# SCH_FIT_MIX_2024-07-01.net
KiCad netlist of a schematic drawn in EasyEDA
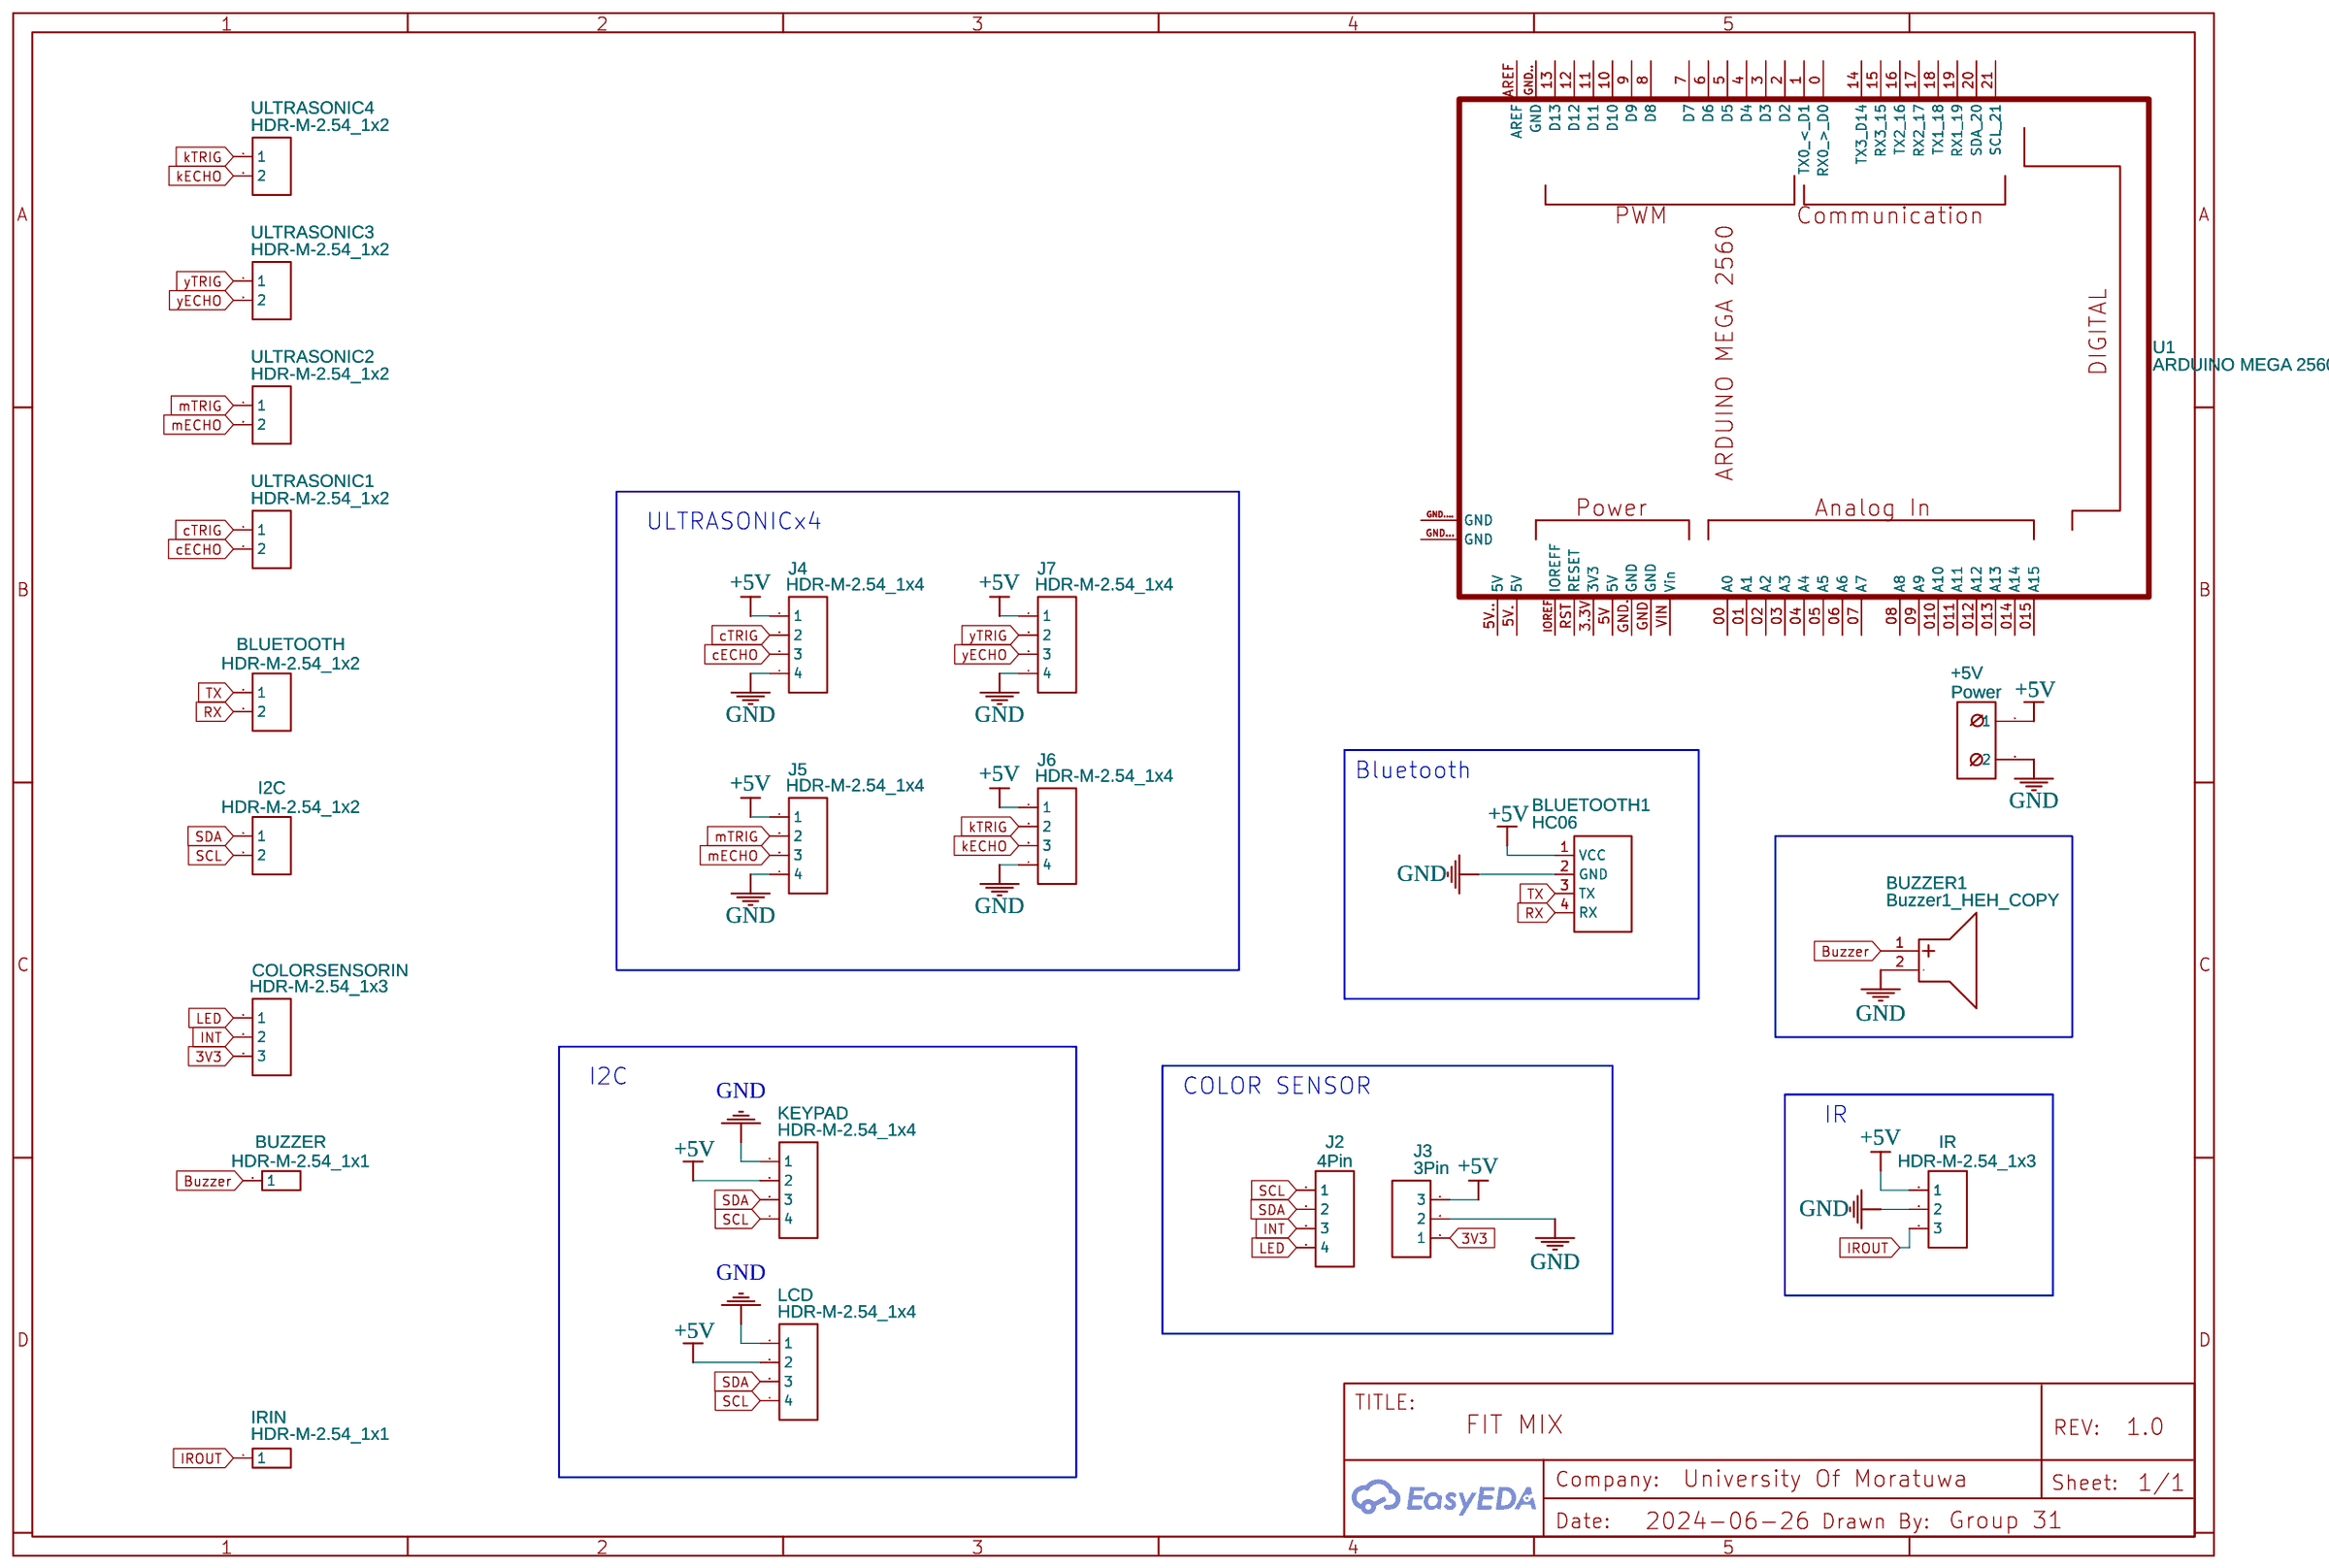
[diagram p0: schematic sheet]

(export (version "E")
  (design (tool "Eeschema 10.0.6"))
  (components
    (comp (ref "+5V") (value "Power") (libsource (lib "") (part "2POSITION_TERMINAL_BLOCK")))
    (comp (ref "BLUETOOTH") (value "HDR-M-2.54_1x2") (libsource (lib "") (part "HDR-M-2.54_1x2_1")))
    (comp (ref "BLUETOOTH1") (value "HC06") (libsource (lib "") (part "HC06")))
    (comp (ref "BUZZER") (value "HDR-M-2.54_1x1") (libsource (lib "") (part "HDR-M-2.54_1x1")))
    (comp (ref "BUZZER1")
      (value "Buzzer1_HEH_COPY")
      (fields (field (name "Manufacturer Part") "-5") (field (name "Manufacturer") "ZLFY"))
      (libsource (lib "") (part "Buzzer1_HEH_COPY"))
    )
    (comp (ref "COLORSENSORIN") (value "HDR-M-2.54_1x3") (libsource (lib "") (part "HDR-M-2.54_1x3")))
    (comp (ref "I2C") (value "HDR-M-2.54_1x2") (libsource (lib "") (part "HDR-M-2.54_1x2_2")))
    (comp (ref "IR") (value "HDR-M-2.54_1x3") (libsource (lib "") (part "HDR-M-2.54_1x3_1")))
    (comp (ref "IRIN") (value "HDR-M-2.54_1x1") (libsource (lib "") (part "HDR-M-2.54_1x1_1")))
    (comp (ref "J2") (value "4Pin") (libsource (lib "") (part "HDR-M-2.54_1x4")))
    (comp (ref "J3") (value "3Pin") (libsource (lib "") (part "HDR-M-2.54_1x3_2")))
    (comp (ref "J4") (value "HDR-M-2.54_1x4") (libsource (lib "") (part "HDR-M-2.54_1x4")))
    (comp (ref "J5") (value "HDR-M-2.54_1x4") (libsource (lib "") (part "HDR-M-2.54_1x4")))
    (comp (ref "J6") (value "HDR-M-2.54_1x4") (libsource (lib "") (part "HDR-M-2.54_1x4")))
    (comp (ref "J7") (value "HDR-M-2.54_1x4") (libsource (lib "") (part "HDR-M-2.54_1x4")))
    (comp (ref "KEYPAD") (value "HDR-M-2.54_1x4") (libsource (lib "") (part "HDR-M-2.54_1x4_2")))
    (comp (ref "LCD") (value "HDR-M-2.54_1x4") (libsource (lib "") (part "HDR-M-2.54_1x4_1")))
    (comp (ref "U1")
      (value "ARDUINO MEGA 2560 R3 V1.0_shella")
      (libsource (lib "") (part "ARDUINO MEGA 2560 R3 V1.0"))
    )
    (comp (ref "ULTRASONIC1") (value "HDR-M-2.54_1x2") (libsource (lib "") (part "HDR-M-2.54_1x2")))
    (comp (ref "ULTRASONIC2") (value "HDR-M-2.54_1x2") (libsource (lib "") (part "HDR-M-2.54_1x2")))
    (comp (ref "ULTRASONIC3") (value "HDR-M-2.54_1x2") (libsource (lib "") (part "HDR-M-2.54_1x2")))
    (comp (ref "ULTRASONIC4") (value "HDR-M-2.54_1x2") (libsource (lib "") (part "HDR-M-2.54_1x2")))
  )
  (nets
    (net (code "1") (name "+5V") (class "Default")
      (node (ref "+5V") (pin "1") (pinfunction "1_1") (pintype "unspecified"))
      (node (ref "BLUETOOTH1") (pin "1") (pinfunction "VCC_1") (pintype "unspecified"))
      (node (ref "IR") (pin "1") (pinfunction "1_1") (pintype "input"))
      (node (ref "J3") (pin "3") (pinfunction "3_3") (pintype "input"))
      (node (ref "J4") (pin "1") (pinfunction "1_1") (pintype "unspecified"))
      (node (ref "J5") (pin "1") (pinfunction "1_1") (pintype "unspecified"))
      (node (ref "J6") (pin "1") (pinfunction "1_1") (pintype "unspecified"))
      (node (ref "J7") (pin "1") (pinfunction "1_1") (pintype "unspecified"))
      (node (ref "KEYPAD") (pin "2") (pinfunction "2_2") (pintype "unspecified"))
      (node (ref "LCD") (pin "2") (pinfunction "2_2") (pintype "unspecified"))
    )
    (net (code "2") (name "3V3") (class "Default")
      (node (ref "COLORSENSORIN") (pin "3") (pinfunction "3_3") (pintype "input"))
      (node (ref "J3") (pin "1") (pinfunction "1_1") (pintype "input"))
    )
    (net (code "3") (name "Buzzer") (class "Default")
      (node (ref "BUZZER") (pin "1") (pinfunction "1_1") (pintype "input"))
      (node (ref "BUZZER1") (pin "1") (pinfunction "+_1") (pintype "unspecified"))
    )
    (net (code "4") (name "GND") (class "Default")
      (node (ref "+5V") (pin "2") (pinfunction "2_2") (pintype "unspecified"))
      (node (ref "BLUETOOTH1") (pin "2") (pinfunction "GND_2") (pintype "unspecified"))
      (node (ref "BUZZER1") (pin "2") (pinfunction "-_2") (pintype "unspecified"))
      (node (ref "IR") (pin "2") (pinfunction "2_2") (pintype "input"))
      (node (ref "J3") (pin "2") (pinfunction "2_2") (pintype "input"))
      (node (ref "J4") (pin "4") (pinfunction "4_4") (pintype "unspecified"))
      (node (ref "J5") (pin "4") (pinfunction "4_4") (pintype "unspecified"))
      (node (ref "J6") (pin "4") (pinfunction "4_4") (pintype "unspecified"))
      (node (ref "J7") (pin "4") (pinfunction "4_4") (pintype "unspecified"))
      (node (ref "KEYPAD") (pin "1") (pinfunction "1_1") (pintype "unspecified"))
      (node (ref "LCD") (pin "1") (pinfunction "1_1") (pintype "unspecified"))
    )
    (net (code "5") (name "INT") (class "Default")
      (node (ref "COLORSENSORIN") (pin "2") (pinfunction "2_2") (pintype "input"))
      (node (ref "J2") (pin "3") (pinfunction "3_3") (pintype "unspecified"))
    )
    (net (code "6") (name "IROUT") (class "Default")
      (node (ref "IR") (pin "3") (pinfunction "3_3") (pintype "input"))
      (node (ref "IRIN") (pin "1") (pinfunction "1_1") (pintype "input"))
    )
    (net (code "7") (name "LED") (class "Default")
      (node (ref "COLORSENSORIN") (pin "1") (pinfunction "1_1") (pintype "input"))
      (node (ref "J2") (pin "4") (pinfunction "4_4") (pintype "unspecified"))
    )
    (net (code "8") (name "RX") (class "Default")
      (node (ref "BLUETOOTH") (pin "2") (pinfunction "2_2") (pintype "unspecified"))
      (node (ref "BLUETOOTH1") (pin "4") (pinfunction "RX_4") (pintype "unspecified"))
    )
    (net (code "9") (name "SCL") (class "Default")
      (node (ref "I2C") (pin "2") (pinfunction "2_2") (pintype "unspecified"))
      (node (ref "J2") (pin "1") (pinfunction "1_1") (pintype "unspecified"))
      (node (ref "KEYPAD") (pin "4") (pinfunction "4_4") (pintype "unspecified"))
      (node (ref "LCD") (pin "4") (pinfunction "4_4") (pintype "unspecified"))
    )
    (net (code "10") (name "SDA") (class "Default")
      (node (ref "I2C") (pin "1") (pinfunction "1_1") (pintype "unspecified"))
      (node (ref "J2") (pin "2") (pinfunction "2_2") (pintype "unspecified"))
      (node (ref "KEYPAD") (pin "3") (pinfunction "3_3") (pintype "unspecified"))
      (node (ref "LCD") (pin "3") (pinfunction "3_3") (pintype "unspecified"))
    )
    (net (code "11") (name "TX") (class "Default")
      (node (ref "BLUETOOTH") (pin "1") (pinfunction "1_1") (pintype "unspecified"))
      (node (ref "BLUETOOTH1") (pin "3") (pinfunction "TX_3") (pintype "unspecified"))
    )
    (net (code "12") (name "cECHO") (class "Default")
      (node (ref "J4") (pin "3") (pinfunction "3_3") (pintype "unspecified"))
      (node (ref "ULTRASONIC1") (pin "2") (pinfunction "2_2") (pintype "unspecified"))
    )
    (net (code "13") (name "cTRIG") (class "Default")
      (node (ref "J4") (pin "2") (pinfunction "2_2") (pintype "unspecified"))
      (node (ref "ULTRASONIC1") (pin "1") (pinfunction "1_1") (pintype "unspecified"))
    )
    (net (code "14") (name "kECHO") (class "Default")
      (node (ref "J6") (pin "3") (pinfunction "3_3") (pintype "unspecified"))
      (node (ref "ULTRASONIC4") (pin "2") (pinfunction "2_2") (pintype "unspecified"))
    )
    (net (code "15") (name "kTRIG") (class "Default")
      (node (ref "J6") (pin "2") (pinfunction "2_2") (pintype "unspecified"))
      (node (ref "ULTRASONIC4") (pin "1") (pinfunction "1_1") (pintype "unspecified"))
    )
    (net (code "16") (name "mECHO") (class "Default")
      (node (ref "J5") (pin "3") (pinfunction "3_3") (pintype "unspecified"))
      (node (ref "ULTRASONIC2") (pin "2") (pinfunction "2_2") (pintype "unspecified"))
    )
    (net (code "17") (name "mTRIG") (class "Default")
      (node (ref "J5") (pin "2") (pinfunction "2_2") (pintype "unspecified"))
      (node (ref "ULTRASONIC2") (pin "1") (pinfunction "1_1") (pintype "unspecified"))
    )
    (net (code "18") (name "unconnected-(U1-3V3-Pad3.3V)") (class "Default")
      (node (ref "U1") (pin "3.3V") (pinfunction "3V3_3.3V") (pintype "unspecified"))
    )
    (net (code "19") (name "unconnected-(U1-5V-Pad5V.)") (class "Default")
      (node (ref "U1") (pin "5V.") (pinfunction "5V_5V.") (pintype "unspecified"))
    )
    (net (code "20") (name "unconnected-(U1-5V-Pad5V..)") (class "Default")
      (node (ref "U1") (pin "5V..") (pinfunction "5V_5V..") (pintype "unspecified"))
    )
    (net (code "21") (name "unconnected-(U1-A0-Pad00)") (class "Default")
      (node (ref "U1") (pin "00") (pinfunction "A0_00") (pintype "unspecified"))
    )
    (net (code "22") (name "unconnected-(U1-A1-Pad01)") (class "Default")
      (node (ref "U1") (pin "01") (pinfunction "A1_01") (pintype "unspecified"))
    )
    (net (code "23") (name "unconnected-(U1-A2-Pad02)") (class "Default")
      (node (ref "U1") (pin "02") (pinfunction "A2_02") (pintype "unspecified"))
    )
    (net (code "24") (name "unconnected-(U1-A3-Pad03)") (class "Default")
      (node (ref "U1") (pin "03") (pinfunction "A3_03") (pintype "unspecified"))
    )
    (net (code "25") (name "unconnected-(U1-A4-Pad04)") (class "Default")
      (node (ref "U1") (pin "04") (pinfunction "A4_04") (pintype "unspecified"))
    )
    (net (code "26") (name "unconnected-(U1-A5-Pad05)") (class "Default")
      (node (ref "U1") (pin "05") (pinfunction "A5_05") (pintype "unspecified"))
    )
    (net (code "27") (name "unconnected-(U1-A6-Pad06)") (class "Default")
      (node (ref "U1") (pin "06") (pinfunction "A6_06") (pintype "unspecified"))
    )
    (net (code "28") (name "unconnected-(U1-A7-Pad07)") (class "Default")
      (node (ref "U1") (pin "07") (pinfunction "A7_07") (pintype "unspecified"))
    )
    (net (code "29") (name "unconnected-(U1-A8-Pad08)") (class "Default")
      (node (ref "U1") (pin "08") (pinfunction "A8_08") (pintype "unspecified"))
    )
    (net (code "30") (name "unconnected-(U1-A9-Pad09)") (class "Default")
      (node (ref "U1") (pin "09") (pinfunction "A9_09") (pintype "unspecified"))
    )
    (net (code "31") (name "unconnected-(U1-A10-Pad010)") (class "Default")
      (node (ref "U1") (pin "010") (pinfunction "A10_010") (pintype "unspecified"))
    )
    (net (code "32") (name "unconnected-(U1-A11-Pad011)") (class "Default")
      (node (ref "U1") (pin "011") (pinfunction "A11_011") (pintype "unspecified"))
    )
    (net (code "33") (name "unconnected-(U1-A12-Pad012)") (class "Default")
      (node (ref "U1") (pin "012") (pinfunction "A12_012") (pintype "unspecified"))
    )
    (net (code "34") (name "unconnected-(U1-A13-Pad013)") (class "Default")
      (node (ref "U1") (pin "013") (pinfunction "A13_013") (pintype "unspecified"))
    )
    (net (code "35") (name "unconnected-(U1-A14-Pad014)") (class "Default")
      (node (ref "U1") (pin "014") (pinfunction "A14_014") (pintype "unspecified"))
    )
    (net (code "36") (name "unconnected-(U1-A15-Pad015)") (class "Default")
      (node (ref "U1") (pin "015") (pinfunction "A15_015") (pintype "unspecified"))
    )
    (net (code "37") (name "unconnected-(U1-D2-Pad2)") (class "Default")
      (node (ref "U1") (pin "2") (pinfunction "D2_2") (pintype "unspecified"))
    )
    (net (code "38") (name "unconnected-(U1-D3-Pad3)") (class "Default")
      (node (ref "U1") (pin "3") (pinfunction "D3_3") (pintype "unspecified"))
    )
    (net (code "39") (name "unconnected-(U1-D4-Pad4)") (class "Default")
      (node (ref "U1") (pin "4") (pinfunction "D4_4") (pintype "unspecified"))
    )
    (net (code "40") (name "unconnected-(U1-D5-Pad5)") (class "Default")
      (node (ref "U1") (pin "5") (pinfunction "D5_5") (pintype "unspecified"))
    )
    (net (code "41") (name "unconnected-(U1-D6-Pad6)") (class "Default")
      (node (ref "U1") (pin "6") (pinfunction "D6_6") (pintype "unspecified"))
    )
    (net (code "42") (name "unconnected-(U1-D7-Pad7)") (class "Default")
      (node (ref "U1") (pin "7") (pinfunction "D7_7") (pintype "unspecified"))
    )
    (net (code "43") (name "unconnected-(U1-D8-Pad8)") (class "Default")
      (node (ref "U1") (pin "8") (pinfunction "D8_8") (pintype "unspecified"))
    )
    (net (code "44") (name "unconnected-(U1-D9-Pad9)") (class "Default")
      (node (ref "U1") (pin "9") (pinfunction "D9_9") (pintype "unspecified"))
    )
    (net (code "45") (name "unconnected-(U1-D10-Pad10)") (class "Default")
      (node (ref "U1") (pin "10") (pinfunction "D10_10") (pintype "unspecified"))
    )
    (net (code "46") (name "unconnected-(U1-D11-Pad11)") (class "Default")
      (node (ref "U1") (pin "11") (pinfunction "D11_11") (pintype "unspecified"))
    )
    (net (code "47") (name "unconnected-(U1-D12-Pad12)") (class "Default")
      (node (ref "U1") (pin "12") (pinfunction "D12_12") (pintype "unspecified"))
    )
    (net (code "48") (name "unconnected-(U1-D13-Pad13)") (class "Default")
      (node (ref "U1") (pin "13") (pinfunction "D13_13") (pintype "unspecified"))
    )
    (net (code "49") (name "unconnected-(U1-GND-PadGND.)") (class "Default")
      (node (ref "U1") (pin "GND.") (pinfunction "GND_GND.") (pintype "unspecified"))
    )
    (net (code "50") (name "unconnected-(U1-GND-PadGND..)") (class "Default")
      (node (ref "U1") (pin "GND..") (pinfunction "GND_GND..") (pintype "unspecified"))
    )
    (net (code "51") (name "unconnected-(U1-GND-PadGND...)") (class "Default")
      (node (ref "U1") (pin "GND...") (pinfunction "GND_GND...") (pintype "unspecified"))
    )
    (net (code "52") (name "unconnected-(U1-GND-PadGND....)") (class "Default")
      (node (ref "U1") (pin "GND....") (pinfunction "GND_GND....") (pintype "unspecified"))
    )
    (net (code "53") (name "unconnected-(U1-IOREFF-PadIOREF)") (class "Default")
      (node (ref "U1") (pin "IOREF") (pinfunction "IOREFF_IOREF") (pintype "unspecified"))
    )
    (net (code "54") (name "unconnected-(U1-Pad5V)") (class "Default")
      (node (ref "U1") (pin "5V") (pinfunction "5V_5V") (pintype "unspecified"))
    )
    (net (code "55") (name "unconnected-(U1-PadAREF)") (class "Default")
      (node (ref "U1") (pin "AREF") (pinfunction "AREF_AREF") (pintype "unspecified"))
    )
    (net (code "56") (name "unconnected-(U1-PadGND)") (class "Default")
      (node (ref "U1") (pin "GND") (pinfunction "GND_GND") (pintype "unspecified"))
    )
    (net (code "57") (name "unconnected-(U1-RESET-PadRST)") (class "Default")
      (node (ref "U1") (pin "RST") (pinfunction "RESET_RST") (pintype "unspecified"))
    )
    (net (code "58") (name "unconnected-(U1-RX0_>_D0-Pad0)") (class "Default")
      (node (ref "U1") (pin "0") (pinfunction "RX0_>_D0_0") (pintype "unspecified"))
    )
    (net (code "59") (name "unconnected-(U1-RX1_19-Pad19)") (class "Default")
      (node (ref "U1") (pin "19") (pinfunction "RX1_19_19") (pintype "unspecified"))
    )
    (net (code "60") (name "unconnected-(U1-RX2_17-Pad17)") (class "Default")
      (node (ref "U1") (pin "17") (pinfunction "RX2_17_17") (pintype "unspecified"))
    )
    (net (code "61") (name "unconnected-(U1-RX3_15-Pad15)") (class "Default")
      (node (ref "U1") (pin "15") (pinfunction "RX3_15_15") (pintype "unspecified"))
    )
    (net (code "62") (name "unconnected-(U1-SCL_21-Pad21)") (class "Default")
      (node (ref "U1") (pin "21") (pinfunction "SCL_21_21") (pintype "unspecified"))
    )
    (net (code "63") (name "unconnected-(U1-SDA_20-Pad20)") (class "Default")
      (node (ref "U1") (pin "20") (pinfunction "SDA_20_20") (pintype "unspecified"))
    )
    (net (code "64") (name "unconnected-(U1-TX0_<_D1-Pad1)") (class "Default")
      (node (ref "U1") (pin "1") (pinfunction "TX0_<_D1_1") (pintype "unspecified"))
    )
    (net (code "65") (name "unconnected-(U1-TX1_18-Pad18)") (class "Default")
      (node (ref "U1") (pin "18") (pinfunction "TX1_18_18") (pintype "unspecified"))
    )
    (net (code "66") (name "unconnected-(U1-TX2_16-Pad16)") (class "Default")
      (node (ref "U1") (pin "16") (pinfunction "TX2_16_16") (pintype "unspecified"))
    )
    (net (code "67") (name "unconnected-(U1-TX3_D14-Pad14)") (class "Default")
      (node (ref "U1") (pin "14") (pinfunction "TX3_D14_14") (pintype "unspecified"))
    )
    (net (code "68") (name "unconnected-(U1-Vin-PadVIN)") (class "Default")
      (node (ref "U1") (pin "VIN") (pinfunction "Vin_VIN") (pintype "unspecified"))
    )
    (net (code "69") (name "yECHO") (class "Default")
      (node (ref "J7") (pin "3") (pinfunction "3_3") (pintype "unspecified"))
      (node (ref "ULTRASONIC3") (pin "2") (pinfunction "2_2") (pintype "unspecified"))
    )
    (net (code "70") (name "yTRIG") (class "Default")
      (node (ref "J7") (pin "2") (pinfunction "2_2") (pintype "unspecified"))
      (node (ref "ULTRASONIC3") (pin "1") (pinfunction "1_1") (pintype "unspecified"))
    )
  )
)
